# SheetPainel.net
KiCad netlist of a schematic drawn in Altium Designer
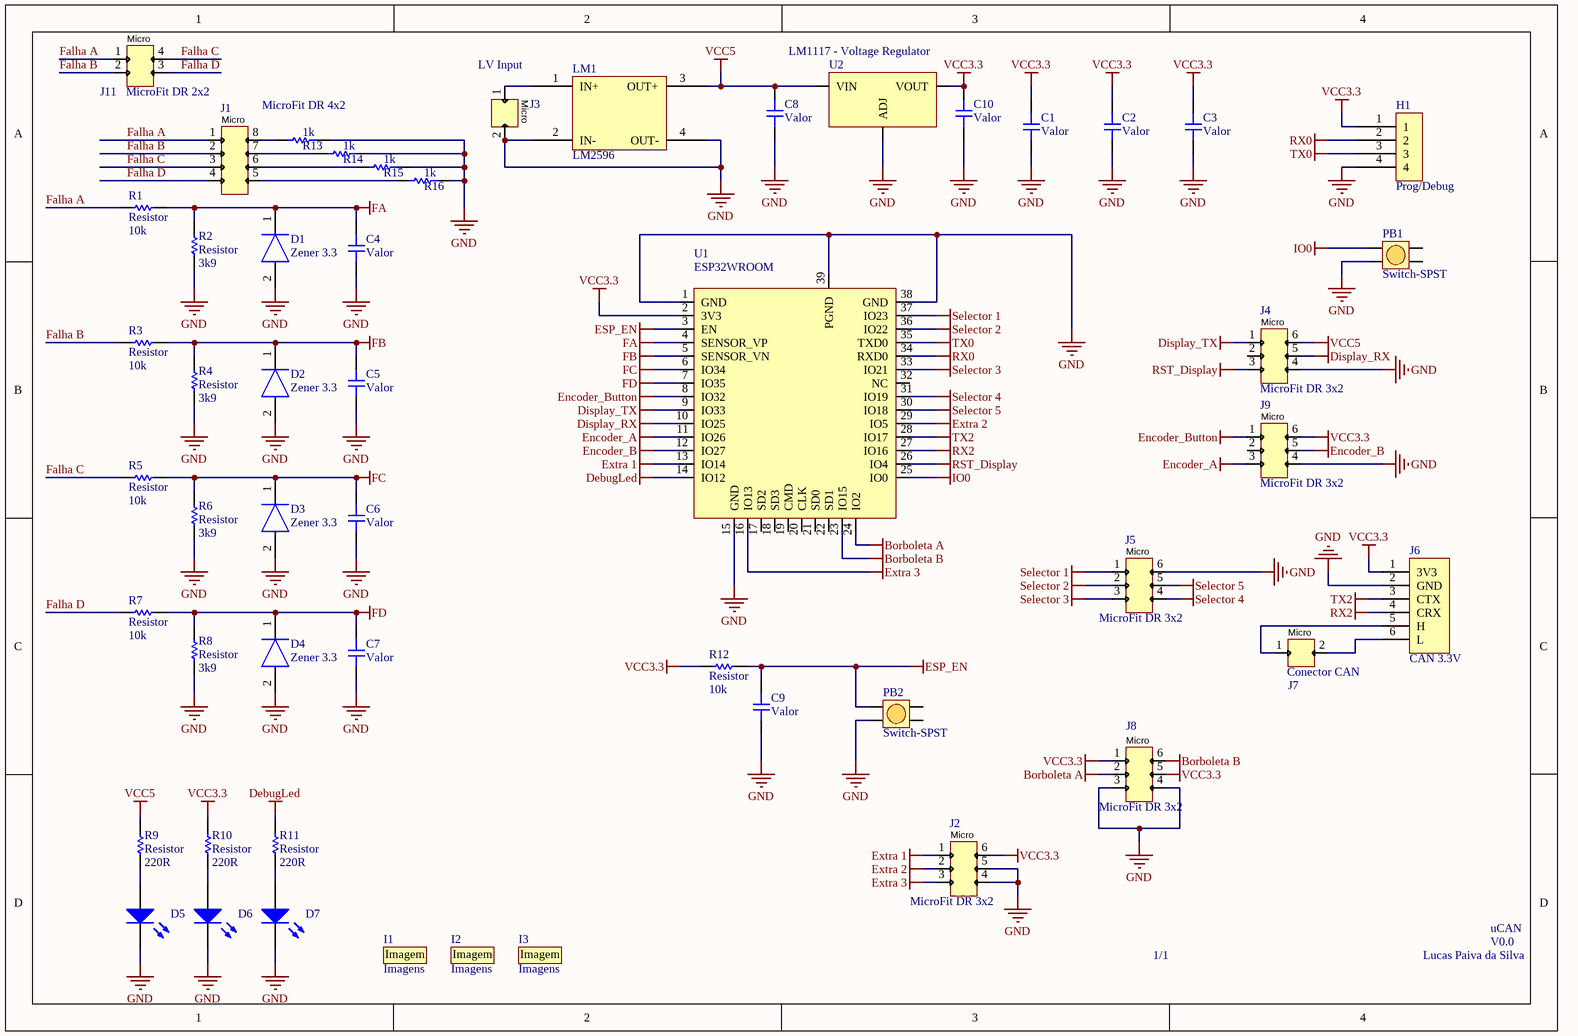
[diagram p0: SheetPainel.SchDoc]

(export (version "E")
  (design (tool "Eeschema 10.0.6"))
  (components
    (comp (ref "C1")
      (value "Valor")
      (footprint "SMD0805C")
      (description "Capacitor")
      (libsource (lib "LIB_Ampera_2021 (1)") (part "Capacitor"))
    )
    (comp (ref "C2")
      (value "Valor")
      (footprint "SMD0805C")
      (description "Capacitor")
      (libsource (lib "LIB_Ampera_2021 (1)") (part "Capacitor"))
    )
    (comp (ref "C3")
      (value "Valor")
      (footprint "SMD0805C")
      (description "Capacitor")
      (libsource (lib "LIB_Ampera_2021 (1)") (part "Capacitor"))
    )
    (comp (ref "C4")
      (value "Valor")
      (footprint "SMD0805C")
      (description "Capacitor")
      (libsource (lib "LIB_Ampera_2021 (1)") (part "Capacitor"))
    )
    (comp (ref "C5")
      (value "Valor")
      (footprint "SMD0805C")
      (description "Capacitor")
      (libsource (lib "LIB_Ampera_2021 (1)") (part "Capacitor"))
    )
    (comp (ref "C6")
      (value "Valor")
      (footprint "SMD0805C")
      (description "Capacitor")
      (libsource (lib "LIB_Ampera_2021 (1)") (part "Capacitor"))
    )
    (comp (ref "C7")
      (value "Valor")
      (footprint "SMD0805C")
      (description "Capacitor")
      (libsource (lib "LIB_Ampera_2021 (1)") (part "Capacitor"))
    )
    (comp (ref "C8")
      (value "Valor")
      (footprint "SMD0805C")
      (description "Capacitor")
      (libsource (lib "LIB_Ampera_2021 (1)") (part "Capacitor"))
    )
    (comp (ref "C9")
      (value "Valor")
      (footprint "SMD0805C")
      (description "Capacitor")
      (libsource (lib "LIB_Ampera_2021 (1)") (part "Capacitor"))
    )
    (comp (ref "C10")
      (value "Valor")
      (footprint "SMD0805C")
      (description "Capacitor")
      (libsource (lib "LIB_Ampera_2021 (1)") (part "Capacitor"))
    )
    (comp (ref "D1")
      (value "Zener 3.3")
      (footprint "CD1408-FU1800")
      (description "Diode Ultrafast")
      (libsource (lib "LIB_Ampera_2021") (part "CD1408-FU1800"))
    )
    (comp (ref "D2")
      (value "Zener 3.3")
      (footprint "CD1408-FU1800")
      (description "Diode Ultrafast")
      (libsource (lib "LIB_Ampera_2021") (part "CD1408-FU1800"))
    )
    (comp (ref "D3")
      (value "Zener 3.3")
      (footprint "CD1408-FU1800")
      (description "Diode Ultrafast")
      (libsource (lib "LIB_Ampera_2021") (part "CD1408-FU1800"))
    )
    (comp (ref "D4")
      (value "Zener 3.3")
      (footprint "CD1408-FU1800")
      (description "Diode Ultrafast")
      (libsource (lib "LIB_Ampera_2021") (part "CD1408-FU1800"))
    )
    (comp (ref "D5")
      (value "LED_SMD")
      (footprint "1206_LED")
      (fields (field (name "PUBLISHER") "Altium Limited"))
      (libsource (lib "LIB_Ampera_2021") (part "LED_SMD"))
    )
    (comp (ref "D6")
      (value "LED_SMD")
      (footprint "1206_LED")
      (fields (field (name "PUBLISHER") "Altium Limited"))
      (libsource (lib "LIB_Ampera_2021") (part "LED_SMD"))
    )
    (comp (ref "D7")
      (value "LED_SMD")
      (footprint "1206_LED")
      (fields (field (name "PUBLISHER") "Altium Limited"))
      (libsource (lib "LIB_Ampera_2021") (part "LED_SMD"))
    )
    (comp (ref "H1")
      (value "Prog/Debug")
      (footprint "Pin Header 1x4 TH Pitch 2.54mm")
      (description "Header 4-pin")
      (libsource (lib "LIB_Ampera_2021") (part "HEADER_4"))
    )
    (comp (ref "I1")
      (value "Imagens")
      (footprint "CARROAMPERA")
      (description "Imagem para retorno")
      (libsource (lib "LIB_Ampera_2021 (1)") (part "Imagens"))
    )
    (comp (ref "I2")
      (value "Imagens")
      (footprint "LOGO AMPERA")
      (description "Imagem para retorno")
      (libsource (lib "LIB_Ampera_2021 (1)") (part "Imagens"))
    )
    (comp (ref "I3")
      (value "Imagens")
      (footprint "LOGO CIRCUIBRAS")
      (description "Imagem para retorno")
      (libsource (lib "LIB_Ampera_2021 (1)") (part "Imagens"))
    )
    (comp (ref "J1")
      (value "MicroFit DR 4x2")
      (footprint "MICRO-FIT 4X2 180° TE")
      (libsource (lib "LIB_Ampera_2021") (part "MicroFit DR 4x2"))
    )
    (comp (ref "J2")
      (value "MicroFit DR 3x2")
      (footprint "MICRO-FIT 3x2 180º MULT")
      (libsource (lib "LIB_Ampera_2021 (1)") (part "MicroFit DR 3x2"))
    )
    (comp (ref "J3")
      (value "LV Input")
      (footprint "MICRO-FIT 2X1 180° TE")
      (libsource (lib "") (part "MicroFit DR 1x2_1"))
    )
    (comp (ref "J4")
      (value "MicroFit DR 3x2")
      (footprint "MICRO-FIT 3x2 180º MULT")
      (libsource (lib "LIB_Ampera_2021 (1)") (part "MicroFit DR 3x2"))
    )
    (comp (ref "J5")
      (value "MicroFit DR 3x2")
      (footprint "MICRO-FIT 3x2 180º MULT")
      (libsource (lib "LIB_Ampera_2021") (part "MicroFit DR 3x2"))
    )
    (comp (ref "J6")
      (value "CAN 3.3V")
      (footprint "CAN3v3")
      (description "CAN Module Acelerometro e giroscopio 3 eixos (I2C)")
      (libsource (lib "LIB_Ampera_2021") (part "CAN 3.3V"))
    )
    (comp (ref "J7")
      (value "Conector CAN")
      (footprint "MICRO-FIT 2X1 180° TE")
      (libsource (lib "LIB_Ampera_2021") (part "MicroFit DR 1x2"))
    )
    (comp (ref "J8")
      (value "MicroFit DR 3x2")
      (footprint "MICRO-FIT 3x2 180º MULT")
      (libsource (lib "LIB_Ampera_2021") (part "MicroFit DR 3x2"))
    )
    (comp (ref "J9")
      (value "MicroFit DR 3x2")
      (footprint "MICRO-FIT 3x2 180º MULT")
      (libsource (lib "LIB_Ampera_2021 (1)") (part "MicroFit DR 3x2"))
    )
    (comp (ref "J11")
      (value "MicroFit DR 2x2")
      (footprint "MICRO-FIT 2x2 180º TE")
      (libsource (lib "LIB_Ampera_2021 (1)") (part "MicroFit DR 2x2"))
    )
    (comp (ref "LM1")
      (value "LM2596")
      (footprint "LM2596")
      (description "Voltage Converter")
      (libsource (lib "LIB_Ampera_2021") (part "LM2596"))
    )
    (comp (ref "PB1")
      (value "Switch-SPST")
      (footprint "TACTILE-6X6")
      (libsource (lib "LIB_Ampera_2021") (part "Switch-SPST"))
    )
    (comp (ref "PB2")
      (value "Switch-SPST")
      (footprint "TACTILE-6X6")
      (libsource (lib "LIB_Ampera_2021") (part "Switch-SPST"))
    )
    (comp (ref "R1")
      (value "Resistor")
      (footprint "RES0805R")
      (fields (field (name "ALTIUM_VALUE") "10k") (field (name "PUBLISHER") "Altium Limited"))
      (libsource (lib "LIB_Ampera_2021 (1)") (part "Resistor-SMD"))
    )
    (comp (ref "R2")
      (value "Resistor")
      (footprint "RES0805R")
      (fields (field (name "ALTIUM_VALUE") "3k9") (field (name "PUBLISHER") "Altium Limited"))
      (libsource (lib "LIB_Ampera_2021 (1)") (part "Resistor-SMD"))
    )
    (comp (ref "R3")
      (value "Resistor")
      (footprint "RES0805R")
      (fields (field (name "ALTIUM_VALUE") "10k") (field (name "PUBLISHER") "Altium Limited"))
      (libsource (lib "LIB_Ampera_2021 (1)") (part "Resistor-SMD"))
    )
    (comp (ref "R4")
      (value "Resistor")
      (footprint "RES0805R")
      (fields (field (name "ALTIUM_VALUE") "3k9") (field (name "PUBLISHER") "Altium Limited"))
      (libsource (lib "LIB_Ampera_2021 (1)") (part "Resistor-SMD"))
    )
    (comp (ref "R5")
      (value "Resistor")
      (footprint "RES0805R")
      (fields (field (name "ALTIUM_VALUE") "10k") (field (name "PUBLISHER") "Altium Limited"))
      (libsource (lib "LIB_Ampera_2021 (1)") (part "Resistor-SMD"))
    )
    (comp (ref "R6")
      (value "Resistor")
      (footprint "RES0805R")
      (fields (field (name "ALTIUM_VALUE") "3k9") (field (name "PUBLISHER") "Altium Limited"))
      (libsource (lib "LIB_Ampera_2021 (1)") (part "Resistor-SMD"))
    )
    (comp (ref "R7")
      (value "Resistor")
      (footprint "RES0805R")
      (fields (field (name "ALTIUM_VALUE") "10k") (field (name "PUBLISHER") "Altium Limited"))
      (libsource (lib "LIB_Ampera_2021 (1)") (part "Resistor-SMD"))
    )
    (comp (ref "R8")
      (value "Resistor")
      (footprint "RES0805R")
      (fields (field (name "ALTIUM_VALUE") "3k9") (field (name "PUBLISHER") "Altium Limited"))
      (libsource (lib "LIB_Ampera_2021 (1)") (part "Resistor-SMD"))
    )
    (comp (ref "R9")
      (value "Resistor")
      (footprint "RES0805R")
      (fields (field (name "ALTIUM_VALUE") "220R") (field (name "PUBLISHER") "Altium Limited"))
      (libsource (lib "LIB_Ampera_2021") (part "Resistor-SMD"))
    )
    (comp (ref "R10")
      (value "Resistor")
      (footprint "RES0805R")
      (fields (field (name "ALTIUM_VALUE") "220R") (field (name "PUBLISHER") "Altium Limited"))
      (libsource (lib "LIB_Ampera_2021") (part "Resistor-SMD"))
    )
    (comp (ref "R11")
      (value "Resistor")
      (footprint "RES0805R")
      (fields (field (name "ALTIUM_VALUE") "220R") (field (name "PUBLISHER") "Altium Limited"))
      (libsource (lib "LIB_Ampera_2021") (part "Resistor-SMD"))
    )
    (comp (ref "R12")
      (value "Resistor")
      (footprint "RES0805R")
      (fields (field (name "ALTIUM_VALUE") "10k") (field (name "PUBLISHER") "Altium Limited"))
      (libsource (lib "LIB_Ampera_2021") (part "Resistor-SMD"))
    )
    (comp (ref "R13")
      (value "1k")
      (footprint "SMD0805R")
      (description "Resistor")
      (libsource (lib "LIB_Ampera_2021 (1)") (part "Resistor"))
    )
    (comp (ref "R14")
      (value "1k")
      (footprint "SMD0805R")
      (description "Resistor")
      (libsource (lib "LIB_Ampera_2021 (1)") (part "Resistor"))
    )
    (comp (ref "R15")
      (value "1k")
      (footprint "SMD0805R")
      (description "Resistor")
      (libsource (lib "LIB_Ampera_2021 (1)") (part "Resistor"))
    )
    (comp (ref "R16")
      (value "1k")
      (footprint "SMD0805R")
      (description "Resistor")
      (libsource (lib "LIB_Ampera_2021 (1)") (part "Resistor"))
    )
    (comp (ref "U1")
      (value "ESP32WROOM")
      (footprint "ESP32WROOM")
      (libsource (lib "LIB_Ampera_2021") (part "ESP32WROOM"))
    )
    (comp (ref "U2")
      (value "LM1117 - Voltage Regulator")
      (footprint "SOT223")
      (libsource (lib "LIB_Ampera_2021 (1)") (part "LM1117 - Voltage Regulator"))
    )
  )
  (nets
    (net (code "1") (name "/Falha A") (class "Default")
      (node (ref "J1") (pin "1") (pinfunction "1_1") (pintype "passive"))
      (node (ref "J11") (pin "1") (pinfunction "1_1") (pintype "passive"))
      (node (ref "R1") (pin "2") (pinfunction "2_2") (pintype "passive"))
    )
    (net (code "2") (name "/Falha B") (class "Default")
      (node (ref "J1") (pin "2") (pinfunction "2_2") (pintype "passive"))
      (node (ref "J11") (pin "2") (pinfunction "2_2") (pintype "passive"))
      (node (ref "R3") (pin "2") (pinfunction "2_2") (pintype "passive"))
    )
    (net (code "3") (name "/Falha C") (class "Default")
      (node (ref "J1") (pin "3") (pinfunction "3_3") (pintype "passive"))
      (node (ref "J11") (pin "4") (pinfunction "4_4") (pintype "passive"))
      (node (ref "R5") (pin "1") (pinfunction "1_1") (pintype "passive"))
    )
    (net (code "4") (name "/Falha D") (class "Default")
      (node (ref "J1") (pin "4") (pinfunction "4_4") (pintype "passive"))
      (node (ref "J11") (pin "3") (pinfunction "3_3") (pintype "passive"))
      (node (ref "R7") (pin "2") (pinfunction "2_2") (pintype "passive"))
    )
    (net (code "5") (name "Borboleta A") (class "Default")
      (node (ref "J8") (pin "2") (pinfunction "2_2") (pintype "passive"))
      (node (ref "U1") (pin "24") (pinfunction "IO2_24") (pintype "passive"))
    )
    (net (code "6") (name "Borboleta B") (class "Default")
      (node (ref "J8") (pin "6") (pinfunction "6_6") (pintype "passive"))
      (node (ref "U1") (pin "23") (pinfunction "IO15_23") (pintype "passive"))
    )
    (net (code "7") (name "DebugLed") (class "Default")
      (node (ref "R11") (pin "1") (pinfunction "1_1") (pintype "passive"))
      (node (ref "U1") (pin "14") (pinfunction "IO12_14") (pintype "passive"))
    )
    (net (code "8") (name "Display_RX") (class "Default")
      (node (ref "J4") (pin "5") (pinfunction "5_5") (pintype "passive"))
      (node (ref "U1") (pin "10") (pinfunction "IO25_10") (pintype "passive"))
    )
    (net (code "9") (name "Display_TX") (class "Default")
      (node (ref "J4") (pin "1") (pinfunction "1_1") (pintype "passive"))
      (node (ref "U1") (pin "9") (pinfunction "IO33_9") (pintype "passive"))
    )
    (net (code "10") (name "ESP_EN") (class "Default")
      (node (ref "C9") (pin "2") (pintype "passive"))
      (node (ref "PB2") (pin "1") (pinfunction "1_1") (pintype "passive"))
      (node (ref "R12") (pin "1") (pinfunction "1_1") (pintype "passive"))
      (node (ref "U1") (pin "3") (pinfunction "EN_3") (pintype "passive"))
    )
    (net (code "11") (name "Encoder_A") (class "Default")
      (node (ref "J9") (pin "3") (pinfunction "3_3") (pintype "passive"))
      (node (ref "U1") (pin "11") (pinfunction "IO26_11") (pintype "passive"))
    )
    (net (code "12") (name "Encoder_B") (class "Default")
      (node (ref "J9") (pin "5") (pinfunction "5_5") (pintype "passive"))
      (node (ref "U1") (pin "12") (pinfunction "IO27_12") (pintype "passive"))
    )
    (net (code "13") (name "Encoder_Button") (class "Default")
      (node (ref "J9") (pin "1") (pinfunction "1_1") (pintype "passive"))
      (node (ref "U1") (pin "8") (pinfunction "IO32_8") (pintype "passive"))
    )
    (net (code "14") (name "Extra 1") (class "Default")
      (node (ref "J2") (pin "1") (pinfunction "1_1") (pintype "passive"))
      (node (ref "U1") (pin "13") (pinfunction "IO14_13") (pintype "passive"))
    )
    (net (code "15") (name "Extra 2") (class "Default")
      (node (ref "J2") (pin "2") (pinfunction "2_2") (pintype "passive"))
      (node (ref "U1") (pin "29") (pinfunction "IO5_29") (pintype "passive"))
    )
    (net (code "16") (name "Extra 3") (class "Default")
      (node (ref "J2") (pin "3") (pinfunction "3_3") (pintype "passive"))
      (node (ref "U1") (pin "16") (pinfunction "IO13_16") (pintype "passive"))
    )
    (net (code "17") (name "FA") (class "Default")
      (node (ref "C4") (pin "2") (pintype "passive"))
      (node (ref "D1") (pin "1") (pinfunction "K_1") (pintype "passive"))
      (node (ref "R1") (pin "1") (pinfunction "1_1") (pintype "passive"))
      (node (ref "R2") (pin "1") (pinfunction "1_1") (pintype "passive"))
      (node (ref "U1") (pin "4") (pinfunction "SENSOR_VP_4") (pintype "passive"))
    )
    (net (code "18") (name "FB") (class "Default")
      (node (ref "C5") (pin "2") (pintype "passive"))
      (node (ref "D2") (pin "1") (pinfunction "K_1") (pintype "passive"))
      (node (ref "R3") (pin "1") (pinfunction "1_1") (pintype "passive"))
      (node (ref "R4") (pin "1") (pinfunction "1_1") (pintype "passive"))
      (node (ref "U1") (pin "5") (pinfunction "SENSOR_VN_5") (pintype "passive"))
    )
    (net (code "19") (name "FC") (class "Default")
      (node (ref "C6") (pin "2") (pintype "passive"))
      (node (ref "D3") (pin "1") (pinfunction "K_1") (pintype "passive"))
      (node (ref "R5") (pin "2") (pinfunction "2_2") (pintype "passive"))
      (node (ref "R6") (pin "2") (pinfunction "2_2") (pintype "passive"))
      (node (ref "U1") (pin "6") (pinfunction "IO34_6") (pintype "passive"))
    )
    (net (code "20") (name "FD") (class "Default")
      (node (ref "C7") (pin "2") (pintype "passive"))
      (node (ref "D4") (pin "1") (pinfunction "K_1") (pintype "passive"))
      (node (ref "R7") (pin "1") (pinfunction "1_1") (pintype "passive"))
      (node (ref "R8") (pin "1") (pinfunction "1_1") (pintype "passive"))
      (node (ref "U1") (pin "7") (pinfunction "IO35_7") (pintype "passive"))
    )
    (net (code "21") (name "GND") (class "Default")
      (node (ref "C1") (pin "1") (pintype "passive"))
      (node (ref "C10") (pin "1") (pintype "passive"))
      (node (ref "C2") (pin "1") (pintype "passive"))
      (node (ref "C3") (pin "1") (pintype "passive"))
      (node (ref "C4") (pin "1") (pintype "passive"))
      (node (ref "C5") (pin "1") (pintype "passive"))
      (node (ref "C6") (pin "1") (pintype "passive"))
      (node (ref "C7") (pin "1") (pintype "passive"))
      (node (ref "C8") (pin "1") (pintype "passive"))
      (node (ref "C9") (pin "1") (pintype "passive"))
      (node (ref "D1") (pin "2") (pinfunction "A_2") (pintype "passive"))
      (node (ref "D2") (pin "2") (pinfunction "A_2") (pintype "passive"))
      (node (ref "D3") (pin "2") (pinfunction "A_2") (pintype "passive"))
      (node (ref "D4") (pin "2") (pinfunction "A_2") (pintype "passive"))
      (node (ref "D5") (pin "K") (pinfunction "K_K") (pintype "passive"))
      (node (ref "D6") (pin "K") (pinfunction "K_K") (pintype "passive"))
      (node (ref "D7") (pin "K") (pinfunction "K_K") (pintype "passive"))
      (node (ref "H1") (pin "4") (pinfunction "4_4") (pintype "passive"))
      (node (ref "J2") (pin "4") (pinfunction "4_4") (pintype "passive"))
      (node (ref "J2") (pin "5") (pinfunction "5_5") (pintype "passive"))
      (node (ref "J3") (pin "2") (pinfunction "2_2") (pintype "passive"))
      (node (ref "J4") (pin "4") (pinfunction "4_4") (pintype "passive"))
      (node (ref "J5") (pin "6") (pinfunction "6_6") (pintype "passive"))
      (node (ref "J6") (pin "2") (pinfunction "GND_2") (pintype "passive"))
      (node (ref "J8") (pin "3") (pinfunction "3_3") (pintype "passive"))
      (node (ref "J8") (pin "4") (pinfunction "4_4") (pintype "passive"))
      (node (ref "J9") (pin "4") (pinfunction "4_4") (pintype "passive"))
      (node (ref "LM1") (pin "2") (pinfunction "IN-_2") (pintype "passive"))
      (node (ref "LM1") (pin "4") (pinfunction "OUT-_4") (pintype "passive"))
      (node (ref "PB1") (pin "2") (pinfunction "2_2") (pintype "passive"))
      (node (ref "PB2") (pin "2") (pinfunction "2_2") (pintype "passive"))
      (node (ref "R13") (pin "2") (pintype "passive"))
      (node (ref "R14") (pin "2") (pintype "passive"))
      (node (ref "R15") (pin "2") (pintype "passive"))
      (node (ref "R16") (pin "2") (pintype "passive"))
      (node (ref "R2") (pin "2") (pinfunction "2_2") (pintype "passive"))
      (node (ref "R4") (pin "2") (pinfunction "2_2") (pintype "passive"))
      (node (ref "R6") (pin "1") (pinfunction "1_1") (pintype "passive"))
      (node (ref "R8") (pin "2") (pinfunction "2_2") (pintype "passive"))
      (node (ref "U1") (pin "1") (pinfunction "GND_1") (pintype "passive"))
      (node (ref "U1") (pin "15") (pinfunction "GND_15") (pintype "passive"))
      (node (ref "U1") (pin "38") (pinfunction "GND_38") (pintype "passive"))
      (node (ref "U1") (pin "39") (pinfunction "PGND_39") (pintype "passive"))
      (node (ref "U2") (pin "1") (pinfunction "ADJ_1") (pintype "passive"))
    )
    (net (code "22") (name "IO0") (class "Default")
      (node (ref "PB1") (pin "1") (pinfunction "1_1") (pintype "passive"))
      (node (ref "U1") (pin "25") (pinfunction "IO0_25") (pintype "passive"))
    )
    (net (code "23") (name "Net-(D5-PadA)") (class "Default")
      (node (ref "D5") (pin "A") (pinfunction "A_A") (pintype "passive"))
      (node (ref "R9") (pin "2") (pinfunction "2_2") (pintype "passive"))
    )
    (net (code "24") (name "Net-(D6-PadA)") (class "Default")
      (node (ref "D6") (pin "A") (pinfunction "A_A") (pintype "passive"))
      (node (ref "R10") (pin "2") (pinfunction "2_2") (pintype "passive"))
    )
    (net (code "25") (name "Net-(D7-PadA)") (class "Default")
      (node (ref "D7") (pin "A") (pinfunction "A_A") (pintype "passive"))
      (node (ref "R11") (pin "2") (pinfunction "2_2") (pintype "passive"))
    )
    (net (code "26") (name "Net-(J1-Pad5)") (class "Default")
      (node (ref "J1") (pin "5") (pinfunction "5_5") (pintype "passive"))
      (node (ref "R16") (pin "1") (pintype "passive"))
    )
    (net (code "27") (name "Net-(J1-Pad6)") (class "Default")
      (node (ref "J1") (pin "6") (pinfunction "6_6") (pintype "passive"))
      (node (ref "R15") (pin "1") (pintype "passive"))
    )
    (net (code "28") (name "Net-(J1-Pad7)") (class "Default")
      (node (ref "J1") (pin "7") (pinfunction "7_7") (pintype "passive"))
      (node (ref "R14") (pin "1") (pintype "passive"))
    )
    (net (code "29") (name "Net-(J1-Pad8)") (class "Default")
      (node (ref "J1") (pin "8") (pinfunction "8_8") (pintype "passive"))
      (node (ref "R13") (pin "1") (pintype "passive"))
    )
    (net (code "30") (name "Net-(J6-H)") (class "Default")
      (node (ref "J6") (pin "5") (pinfunction "H_5") (pintype "passive"))
      (node (ref "J7") (pin "1") (pinfunction "1_1") (pintype "passive"))
    )
    (net (code "31") (name "Net-(J6-L)") (class "Default")
      (node (ref "J6") (pin "6") (pinfunction "L_6") (pintype "passive"))
      (node (ref "J7") (pin "2") (pinfunction "2_2") (pintype "passive"))
    )
    (net (code "32") (name "Net-(LM1-IN+)") (class "Default")
      (node (ref "J3") (pin "1") (pinfunction "1_1") (pintype "passive"))
      (node (ref "LM1") (pin "1") (pinfunction "IN+_1") (pintype "passive"))
    )
    (net (code "33") (name "RST_Display") (class "Default")
      (node (ref "J4") (pin "3") (pinfunction "3_3") (pintype "passive"))
      (node (ref "U1") (pin "26") (pinfunction "IO4_26") (pintype "passive"))
    )
    (net (code "34") (name "RX0") (class "Default")
      (node (ref "H1") (pin "2") (pinfunction "2_2") (pintype "passive"))
      (node (ref "U1") (pin "34") (pinfunction "RXD0_34") (pintype "passive"))
    )
    (net (code "35") (name "RX2") (class "Default")
      (node (ref "J6") (pin "4") (pinfunction "CRX_4") (pintype "passive"))
      (node (ref "U1") (pin "27") (pinfunction "IO16_27") (pintype "passive"))
    )
    (net (code "36") (name "Selector 1") (class "Default")
      (node (ref "J5") (pin "1") (pinfunction "1_1") (pintype "passive"))
      (node (ref "U1") (pin "37") (pinfunction "IO23_37") (pintype "passive"))
    )
    (net (code "37") (name "Selector 2") (class "Default")
      (node (ref "J5") (pin "2") (pinfunction "2_2") (pintype "passive"))
      (node (ref "U1") (pin "36") (pinfunction "IO22_36") (pintype "passive"))
    )
    (net (code "38") (name "Selector 3") (class "Default")
      (node (ref "J5") (pin "3") (pinfunction "3_3") (pintype "passive"))
      (node (ref "U1") (pin "33") (pinfunction "IO21_33") (pintype "passive"))
    )
    (net (code "39") (name "Selector 4") (class "Default")
      (node (ref "J5") (pin "4") (pinfunction "4_4") (pintype "passive"))
      (node (ref "U1") (pin "31") (pinfunction "IO19_31") (pintype "passive"))
    )
    (net (code "40") (name "Selector 5") (class "Default")
      (node (ref "J5") (pin "5") (pinfunction "5_5") (pintype "passive"))
      (node (ref "U1") (pin "30") (pinfunction "IO18_30") (pintype "passive"))
    )
    (net (code "41") (name "TX0") (class "Default")
      (node (ref "H1") (pin "3") (pinfunction "3_3") (pintype "passive"))
      (node (ref "U1") (pin "35") (pinfunction "TXD0_35") (pintype "passive"))
    )
    (net (code "42") (name "TX2") (class "Default")
      (node (ref "J6") (pin "3") (pinfunction "CTX_3") (pintype "passive"))
      (node (ref "U1") (pin "28") (pinfunction "IO17_28") (pintype "passive"))
    )
    (net (code "43") (name "VCC3.3") (class "Default")
      (node (ref "C1") (pin "2") (pintype "passive"))
      (node (ref "C10") (pin "2") (pintype "passive"))
      (node (ref "C2") (pin "2") (pintype "passive"))
      (node (ref "C3") (pin "2") (pintype "passive"))
      (node (ref "H1") (pin "1") (pinfunction "1_1") (pintype "passive"))
      (node (ref "J2") (pin "6") (pinfunction "6_6") (pintype "passive"))
      (node (ref "J6") (pin "1") (pinfunction "3V3_1") (pintype "passive"))
      (node (ref "J8") (pin "1") (pinfunction "1_1") (pintype "passive"))
      (node (ref "J8") (pin "5") (pinfunction "5_5") (pintype "passive"))
      (node (ref "J9") (pin "6") (pinfunction "6_6") (pintype "passive"))
      (node (ref "R10") (pin "1") (pinfunction "1_1") (pintype "passive"))
      (node (ref "R12") (pin "2") (pinfunction "2_2") (pintype "passive"))
      (node (ref "U1") (pin "2") (pinfunction "3V3_2") (pintype "passive"))
      (node (ref "U2") (pin "2") (pinfunction "VOUT_2") (pintype "passive"))
    )
    (net (code "44") (name "VCC5") (class "Default")
      (node (ref "C8") (pin "2") (pintype "passive"))
      (node (ref "J4") (pin "6") (pinfunction "6_6") (pintype "passive"))
      (node (ref "LM1") (pin "3") (pinfunction "OUT+_3") (pintype "passive"))
      (node (ref "R9") (pin "1") (pinfunction "1_1") (pintype "passive"))
      (node (ref "U2") (pin "3") (pinfunction "VIN_3") (pintype "passive"))
    )
    (net (code "45") (name "unconnected-(J4-Pad2)") (class "Default")
      (node (ref "J4") (pin "2") (pinfunction "2_2") (pintype "passive"))
    )
    (net (code "46") (name "unconnected-(J9-Pad2)") (class "Default")
      (node (ref "J9") (pin "2") (pinfunction "2_2") (pintype "passive"))
    )
    (net (code "47") (name "unconnected-(PB1-Pad3)") (class "Default")
      (node (ref "PB1") (pin "3") (pinfunction "3_3") (pintype "passive"))
    )
    (net (code "48") (name "unconnected-(PB1-Pad4)") (class "Default")
      (node (ref "PB1") (pin "4") (pinfunction "4_4") (pintype "passive"))
    )
    (net (code "49") (name "unconnected-(PB2-Pad3)") (class "Default")
      (node (ref "PB2") (pin "3") (pinfunction "3_3") (pintype "passive"))
    )
    (net (code "50") (name "unconnected-(PB2-Pad4)") (class "Default")
      (node (ref "PB2") (pin "4") (pinfunction "4_4") (pintype "passive"))
    )
    (net (code "51") (name "unconnected-(U1-CLK-Pad20)") (class "Default")
      (node (ref "U1") (pin "20") (pinfunction "CLK_20") (pintype "passive"))
    )
    (net (code "52") (name "unconnected-(U1-CMD-Pad19)") (class "Default")
      (node (ref "U1") (pin "19") (pinfunction "CMD_19") (pintype "passive"))
    )
    (net (code "53") (name "unconnected-(U1-NC-Pad32)") (class "Default")
      (node (ref "U1") (pin "32") (pinfunction "NC_32") (pintype "passive"))
    )
    (net (code "54") (name "unconnected-(U1-SD0-Pad21)") (class "Default")
      (node (ref "U1") (pin "21") (pinfunction "SD0_21") (pintype "passive"))
    )
    (net (code "55") (name "unconnected-(U1-SD1-Pad22)") (class "Default")
      (node (ref "U1") (pin "22") (pinfunction "SD1_22") (pintype "passive"))
    )
    (net (code "56") (name "unconnected-(U1-SD2-Pad17)") (class "Default")
      (node (ref "U1") (pin "17") (pinfunction "SD2_17") (pintype "passive"))
    )
    (net (code "57") (name "unconnected-(U1-SD3-Pad18)") (class "Default")
      (node (ref "U1") (pin "18") (pinfunction "SD3_18") (pintype "passive"))
    )
  )
)
